# HUD.net
KiCad netlist of a schematic drawn in Altium Designer
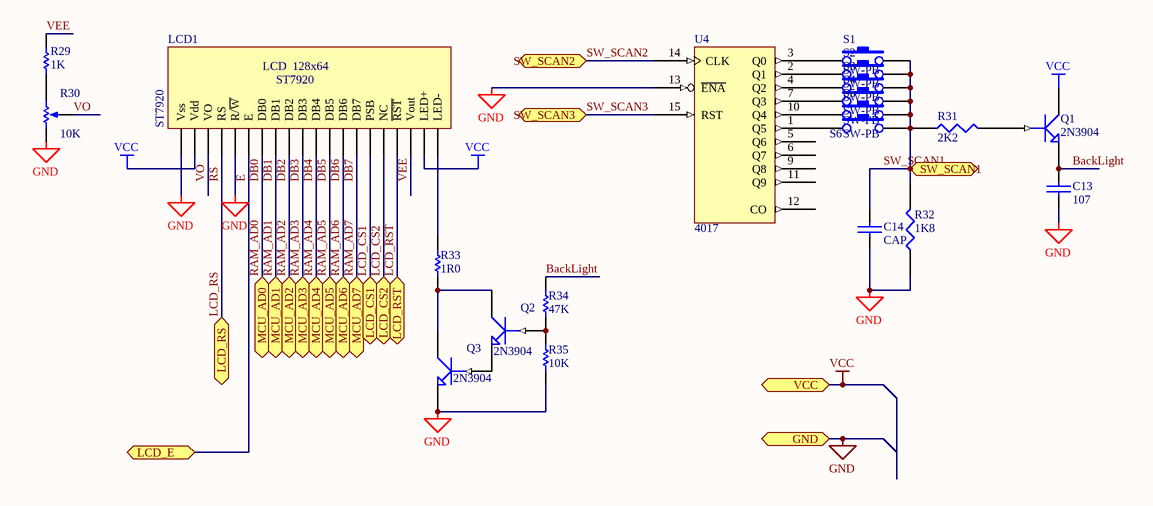
[diagram p0: HUD.SchDoc]

(export (version "E")
  (design (tool "Eeschema 10.0.6"))
  (components
    (comp (ref "C13")
      (value "107")
      (footprint "SMC_D/WA")
      (description "Capacitor")
      (libsource (lib "*") (part "CAP"))
    )
    (comp (ref "C14")
      (value "CAP")
      (footprint "6-0805_N")
      (description "Capacitor")
      (libsource (lib "*") (part "CAP"))
    )
    (comp (ref "LCD1")
      (value "ST7920")
      (footprint "LCD12864B")
      (description "ST7920 LCD128X64")
      (libsource (lib "Schlib1") (part "ST7920"))
    )
    (comp (ref "Q1")
      (value "2N3904")
      (footprint "SOT-23")
      (description "NPN Transistor")
      (libsource (lib "*") (part "NPN1"))
    )
    (comp (ref "Q2")
      (value "2N3904")
      (footprint "SOT-23")
      (description "NPN Transistor")
      (libsource (lib "*") (part "NPN1"))
    )
    (comp (ref "Q3")
      (value "2N3904")
      (footprint "SOT-23")
      (description "NPN Transistor")
      (libsource (lib "*") (part "NPN1"))
    )
    (comp (ref "R29")
      (value "1K")
      (footprint "6-0805_N")
      (description "Semiconductor Resistor")
      (fields (field (name "PUBLISHER") "Altium Limited"))
      (libsource (lib "*") (part "Res Semi"))
    )
    (comp (ref "R30")
      (value "10K")
      (footprint "BTXANH")
      (description "Potentiometer")
      (fields (field (name "PUBLISHER") "*"))
      (libsource (lib "*") (part "RPot"))
    )
    (comp (ref "R31") (value "2K2") (footprint "6-0805_N") (libsource (lib "*") (part "RES1")))
    (comp (ref "R32") (value "1K8") (footprint "6-0805_N") (libsource (lib "*") (part "RES1")))
    (comp (ref "R33")
      (value "1R0")
      (footprint "6-0805_N")
      (description "Semiconductor Resistor")
      (fields (field (name "PUBLISHER") "Altium Limited"))
      (libsource (lib "*") (part "Res Semi"))
    )
    (comp (ref "R34")
      (value "47K")
      (footprint "6-0805_N")
      (description "Semiconductor Resistor")
      (fields (field (name "PUBLISHER") "Altium Limited"))
      (libsource (lib "*") (part "Res Semi"))
    )
    (comp (ref "R35")
      (value "10K")
      (footprint "6-0805_N")
      (description "Semiconductor Resistor")
      (fields (field (name "PUBLISHER") "Altium Limited"))
      (libsource (lib "*") (part "Res Semi"))
    )
    (comp (ref "S1") (value "SW-PB") (footprint "CTCHIP_TO") (libsource (lib "*") (part "SW-PB")))
    (comp (ref "S2") (value "SW-PB") (footprint "CTCHIP_TO") (libsource (lib "*") (part "SW-PB")))
    (comp (ref "S3") (value "SW-PB") (footprint "CTCHIP_TO") (libsource (lib "*") (part "SW-PB")))
    (comp (ref "S4") (value "SW-PB") (footprint "CTCHIP_TO") (libsource (lib "*") (part "SW-PB")))
    (comp (ref "S5") (value "SW-PB") (footprint "CTCHIP_TO") (libsource (lib "*") (part "SW-PB")))
    (comp (ref "S6") (value "SW-PB") (footprint "CTCHIP_TO") (libsource (lib "*") (part "SW-PB")))
    (comp (ref "U4") (value "4017") (footprint "SO16") (libsource (lib "*") (part "4017")))
  )
  (nets
    (net (code "1") (name "/BackLight") (class "Default")
      (node (ref "C13") (pin "1") (pinfunction "1_1") (pintype "passive"))
      (node (ref "Q1") (pin "2") (pinfunction "E_2") (pintype "passive"))
      (node (ref "R34") (pin "2") (pinfunction "2_2") (pintype "passive"))
    )
    (net (code "2") (name "/DB0") (class "Default")
      (node (ref "LCD1") (pin "7") (pinfunction "DB0_7") (pintype "passive"))
    )
    (net (code "3") (name "/DB1") (class "Default")
      (node (ref "LCD1") (pin "8") (pinfunction "DB1_8") (pintype "passive"))
    )
    (net (code "4") (name "/DB2") (class "Default")
      (node (ref "LCD1") (pin "9") (pinfunction "DB2_9") (pintype "passive"))
    )
    (net (code "5") (name "/DB3") (class "Default")
      (node (ref "LCD1") (pin "10") (pinfunction "DB3_10") (pintype "passive"))
    )
    (net (code "6") (name "/DB4") (class "Default")
      (node (ref "LCD1") (pin "11") (pinfunction "DB4_11") (pintype "passive"))
    )
    (net (code "7") (name "/DB5") (class "Default")
      (node (ref "LCD1") (pin "12") (pinfunction "DB5_12") (pintype "passive"))
    )
    (net (code "8") (name "/DB6") (class "Default")
      (node (ref "LCD1") (pin "13") (pinfunction "DB6_13") (pintype "passive"))
    )
    (net (code "9") (name "/DB7") (class "Default")
      (node (ref "LCD1") (pin "14") (pinfunction "DB7_14") (pintype "passive"))
    )
    (net (code "10") (name "/E") (class "Default")
      (node (ref "LCD1") (pin "6") (pinfunction "E_6") (pintype "passive"))
    )
    (net (code "11") (name "/LCD_CS1") (class "Default")
      (node (ref "LCD1") (pin "15") (pinfunction "PSB_15") (pintype "passive"))
    )
    (net (code "12") (name "/LCD_CS2") (class "Default")
      (node (ref "LCD1") (pin "16") (pinfunction "NC_16") (pintype "passive"))
    )
    (net (code "13") (name "/LCD_RS") (class "Default")
      (node (ref "LCD1") (pin "4") (pinfunction "RS_4") (pintype "passive"))
    )
    (net (code "14") (name "/LCD_RST") (class "Default")
      (node (ref "LCD1") (pin "17") (pinfunction "~{RST}_17") (pintype "passive"))
    )
    (net (code "15") (name "/SW_SCAN1") (class "Default")
      (node (ref "C14") (pin "1") (pinfunction "1_1") (pintype "passive"))
      (node (ref "R31") (pin "1") (pinfunction "1_1") (pintype "passive"))
      (node (ref "R32") (pin "2") (pinfunction "2_2") (pintype "passive"))
      (node (ref "S1") (pin "2") (pinfunction "2_2") (pintype "passive"))
      (node (ref "S2") (pin "2") (pinfunction "2_2") (pintype "passive"))
      (node (ref "S3") (pin "2") (pinfunction "2_2") (pintype "passive"))
      (node (ref "S4") (pin "2") (pinfunction "2_2") (pintype "passive"))
      (node (ref "S5") (pin "2") (pinfunction "2_2") (pintype "passive"))
      (node (ref "S6") (pin "2") (pinfunction "2_2") (pintype "passive"))
    )
    (net (code "16") (name "/SW_SCAN2") (class "Default")
      (node (ref "U4") (pin "14") (pinfunction "CLK_14") (pintype "input"))
    )
    (net (code "17") (name "/SW_SCAN3") (class "Default")
      (node (ref "U4") (pin "15") (pinfunction "RST_15") (pintype "input"))
    )
    (net (code "18") (name "/VEE") (class "Default")
      (node (ref "LCD1") (pin "18") (pinfunction "Vout_18") (pintype "passive"))
      (node (ref "R29") (pin "2") (pinfunction "2_2") (pintype "passive"))
    )
    (net (code "19") (name "/VO") (class "Default")
      (node (ref "LCD1") (pin "3") (pinfunction "VO_3") (pintype "passive"))
      (node (ref "R30") (pin "2") (pinfunction "TAP_2") (pintype "passive"))
    )
    (net (code "20") (name "GND") (class "Default")
      (node (ref "C13") (pin "2") (pinfunction "2_2") (pintype "passive"))
      (node (ref "C14") (pin "2") (pinfunction "2_2") (pintype "passive"))
      (node (ref "LCD1") (pin "1") (pinfunction "Vss_1") (pintype "passive"))
      (node (ref "LCD1") (pin "5") (pinfunction "R/~{W}_5") (pintype "passive"))
      (node (ref "Q3") (pin "2") (pinfunction "E_2") (pintype "passive"))
      (node (ref "R30") (pin "1") (pinfunction "TOP_1") (pintype "passive"))
      (node (ref "R32") (pin "1") (pinfunction "1_1") (pintype "passive"))
      (node (ref "R35") (pin "1") (pinfunction "1_1") (pintype "passive"))
      (node (ref "U4") (pin "13") (pinfunction "~{ENA}_13") (pintype "input"))
      (node (ref "U4") (pin "8") (pinfunction "GND_8") (pintype "power_in"))
    )
    (net (code "21") (name "Net-(LCD1-LED-)") (class "Default")
      (node (ref "LCD1") (pin "20") (pinfunction "LED-_20") (pintype "passive"))
      (node (ref "R33") (pin "2") (pinfunction "2_2") (pintype "passive"))
    )
    (net (code "22") (name "Net-(Q1-B)") (class "Default")
      (node (ref "Q1") (pin "1") (pinfunction "B_1") (pintype "input"))
      (node (ref "R31") (pin "2") (pinfunction "2_2") (pintype "passive"))
    )
    (net (code "23") (name "Net-(Q2-B)") (class "Default")
      (node (ref "Q2") (pin "1") (pinfunction "B_1") (pintype "input"))
      (node (ref "R34") (pin "1") (pinfunction "1_1") (pintype "passive"))
      (node (ref "R35") (pin "2") (pinfunction "2_2") (pintype "passive"))
    )
    (net (code "24") (name "Net-(Q2-C)") (class "Default")
      (node (ref "Q2") (pin "3") (pinfunction "C_3") (pintype "passive"))
      (node (ref "Q3") (pin "3") (pinfunction "C_3") (pintype "passive"))
      (node (ref "R33") (pin "1") (pinfunction "1_1") (pintype "passive"))
    )
    (net (code "25") (name "Net-(Q2-E)") (class "Default")
      (node (ref "Q2") (pin "2") (pinfunction "E_2") (pintype "passive"))
      (node (ref "Q3") (pin "1") (pinfunction "B_1") (pintype "input"))
    )
    (net (code "26") (name "Net-(R30-BOT)") (class "Default")
      (node (ref "R29") (pin "1") (pinfunction "1_1") (pintype "passive"))
      (node (ref "R30") (pin "3") (pinfunction "BOT_3") (pintype "passive"))
    )
    (net (code "27") (name "Net-(U4-Q0)") (class "Default")
      (node (ref "S1") (pin "1") (pinfunction "1_1") (pintype "passive"))
      (node (ref "U4") (pin "3") (pinfunction "Q0_3") (pintype "output"))
    )
    (net (code "28") (name "Net-(U4-Q1)") (class "Default")
      (node (ref "S2") (pin "1") (pinfunction "1_1") (pintype "passive"))
      (node (ref "U4") (pin "2") (pinfunction "Q1_2") (pintype "output"))
    )
    (net (code "29") (name "Net-(U4-Q2)") (class "Default")
      (node (ref "S3") (pin "1") (pinfunction "1_1") (pintype "passive"))
      (node (ref "U4") (pin "4") (pinfunction "Q2_4") (pintype "output"))
    )
    (net (code "30") (name "Net-(U4-Q3)") (class "Default")
      (node (ref "S4") (pin "1") (pinfunction "1_1") (pintype "passive"))
      (node (ref "U4") (pin "7") (pinfunction "Q3_7") (pintype "output"))
    )
    (net (code "31") (name "Net-(U4-Q4)") (class "Default")
      (node (ref "S5") (pin "1") (pinfunction "1_1") (pintype "passive"))
      (node (ref "U4") (pin "10") (pinfunction "Q4_10") (pintype "output"))
    )
    (net (code "32") (name "Net-(U4-Q5)") (class "Default")
      (node (ref "S6") (pin "1") (pinfunction "1_1") (pintype "passive"))
      (node (ref "U4") (pin "1") (pinfunction "Q5_1") (pintype "output"))
    )
    (net (code "33") (name "VCC") (class "Default")
      (node (ref "LCD1") (pin "19") (pinfunction "LED+_19") (pintype "passive"))
      (node (ref "LCD1") (pin "2") (pinfunction "Vdd_2") (pintype "passive"))
      (node (ref "Q1") (pin "3") (pinfunction "C_3") (pintype "passive"))
      (node (ref "U4") (pin "16") (pinfunction "VCC_16") (pintype "power_in"))
    )
    (net (code "34") (name "unconnected-(U4-CO-Pad12)") (class "Default")
      (node (ref "U4") (pin "12") (pinfunction "CO_12") (pintype "output"))
    )
    (net (code "35") (name "unconnected-(U4-Q6-Pad5)") (class "Default")
      (node (ref "U4") (pin "5") (pinfunction "Q6_5") (pintype "output"))
    )
    (net (code "36") (name "unconnected-(U4-Q7-Pad6)") (class "Default")
      (node (ref "U4") (pin "6") (pinfunction "Q7_6") (pintype "output"))
    )
    (net (code "37") (name "unconnected-(U4-Q8-Pad9)") (class "Default")
      (node (ref "U4") (pin "9") (pinfunction "Q8_9") (pintype "output"))
    )
    (net (code "38") (name "unconnected-(U4-Q9-Pad11)") (class "Default")
      (node (ref "U4") (pin "11") (pinfunction "Q9_11") (pintype "output"))
    )
  )
)
